# clock.net
KiCad netlist of a schematic drawn in Altium Designer
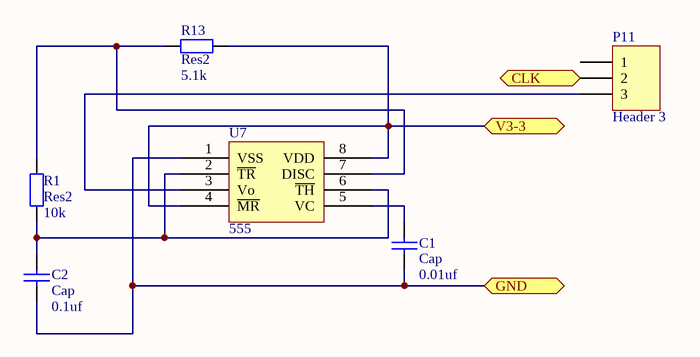
[diagram p0: clock.SchDoc]

(export (version "E")
  (design (tool "Eeschema 10.0.6"))
  (components
    (comp (ref "C1")
      (value "Cap")
      (footprint "0603")
      (description "Capacitor")
      (fields (field (name "ALTIUM_VALUE") "0.01uf") (field (name "PUBLISHER") "Altium Limited"))
      (libsource (lib "Miscellaneous Devices") (part "Cap"))
    )
    (comp (ref "C2")
      (value "Cap")
      (footprint "0603")
      (description "Capacitor")
      (fields (field (name "ALTIUM_VALUE") "0.1uf") (field (name "PUBLISHER") "Altium Limited"))
      (libsource (lib "Miscellaneous Devices") (part "Cap"))
    )
    (comp (ref "P11")
      (value "Header 3")
      (footprint "HDR1X3")
      (description "Header, 3-Pin")
      (fields (field (name "PUBLISHER") "Altium Limited"))
      (libsource (lib "Miscellaneous Connectors") (part "Header 3"))
    )
    (comp (ref "R1")
      (value "Res2")
      (footprint "0603")
      (description "Resistor")
      (fields (field (name "ALTIUM_VALUE") "10k") (field (name "PUBLISHER") "Altium Limited"))
      (libsource (lib "Miscellaneous Devices") (part "Res2"))
    )
    (comp (ref "R13")
      (value "Res2")
      (footprint "0603")
      (description "Resistor")
      (fields (field (name "ALTIUM_VALUE") "5.1k") (field (name "PUBLISHER") "Altium Limited"))
      (libsource (lib "") (part "Res2_1"))
    )
    (comp (ref "U7") (value "555") (footprint "SOP-8") (libsource (lib "mylib") (part "NE555")))
  )
  (nets
    (net (code "1") (name "/CLK") (class "Default")
      (node (ref "P11") (pin "2") (pinfunction "2_2") (pintype "passive"))
    )
    (net (code "2") (name "/GND") (class "Default")
      (node (ref "C1") (pin "1") (pinfunction "1_1") (pintype "passive"))
      (node (ref "C2") (pin "1") (pinfunction "1_1") (pintype "passive"))
      (node (ref "U7") (pin "1") (pinfunction "VSS_1") (pintype "passive"))
    )
    (net (code "3") (name "/V3-3") (class "Default")
      (node (ref "R13") (pin "1") (pinfunction "1_1") (pintype "passive"))
      (node (ref "U7") (pin "4") (pinfunction "~{MR}_4") (pintype "passive"))
      (node (ref "U7") (pin "8") (pinfunction "VDD_8") (pintype "passive"))
    )
    (net (code "4") (name "Net-(U7-DISC)") (class "Default")
      (node (ref "R1") (pin "2") (pinfunction "2_2") (pintype "passive"))
      (node (ref "R13") (pin "2") (pinfunction "2_2") (pintype "passive"))
      (node (ref "U7") (pin "7") (pinfunction "DISC_7") (pintype "passive"))
    )
    (net (code "5") (name "Net-(U7-VC)") (class "Default")
      (node (ref "C1") (pin "2") (pinfunction "2_2") (pintype "passive"))
      (node (ref "U7") (pin "5") (pinfunction "VC_5") (pintype "passive"))
    )
    (net (code "6") (name "Net-(U7-Vo)") (class "Default")
      (node (ref "P11") (pin "3") (pinfunction "3_3") (pintype "passive"))
      (node (ref "U7") (pin "3") (pinfunction "Vo_3") (pintype "passive"))
    )
    (net (code "7") (name "Net-(U7-~{TH})") (class "Default")
      (node (ref "C2") (pin "2") (pinfunction "2_2") (pintype "passive"))
      (node (ref "R1") (pin "1") (pinfunction "1_1") (pintype "passive"))
      (node (ref "U7") (pin "2") (pinfunction "~{TR}_2") (pintype "passive"))
      (node (ref "U7") (pin "6") (pinfunction "~{TH}_6") (pintype "passive"))
    )
    (net (code "8") (name "unconnected-(P11-Pad1)") (class "Default")
      (node (ref "P11") (pin "1") (pinfunction "1_1") (pintype "passive"))
    )
  )
)
